# raspdancer21_1_0.net
KiCad netlist of a schematic drawn in EAGLE
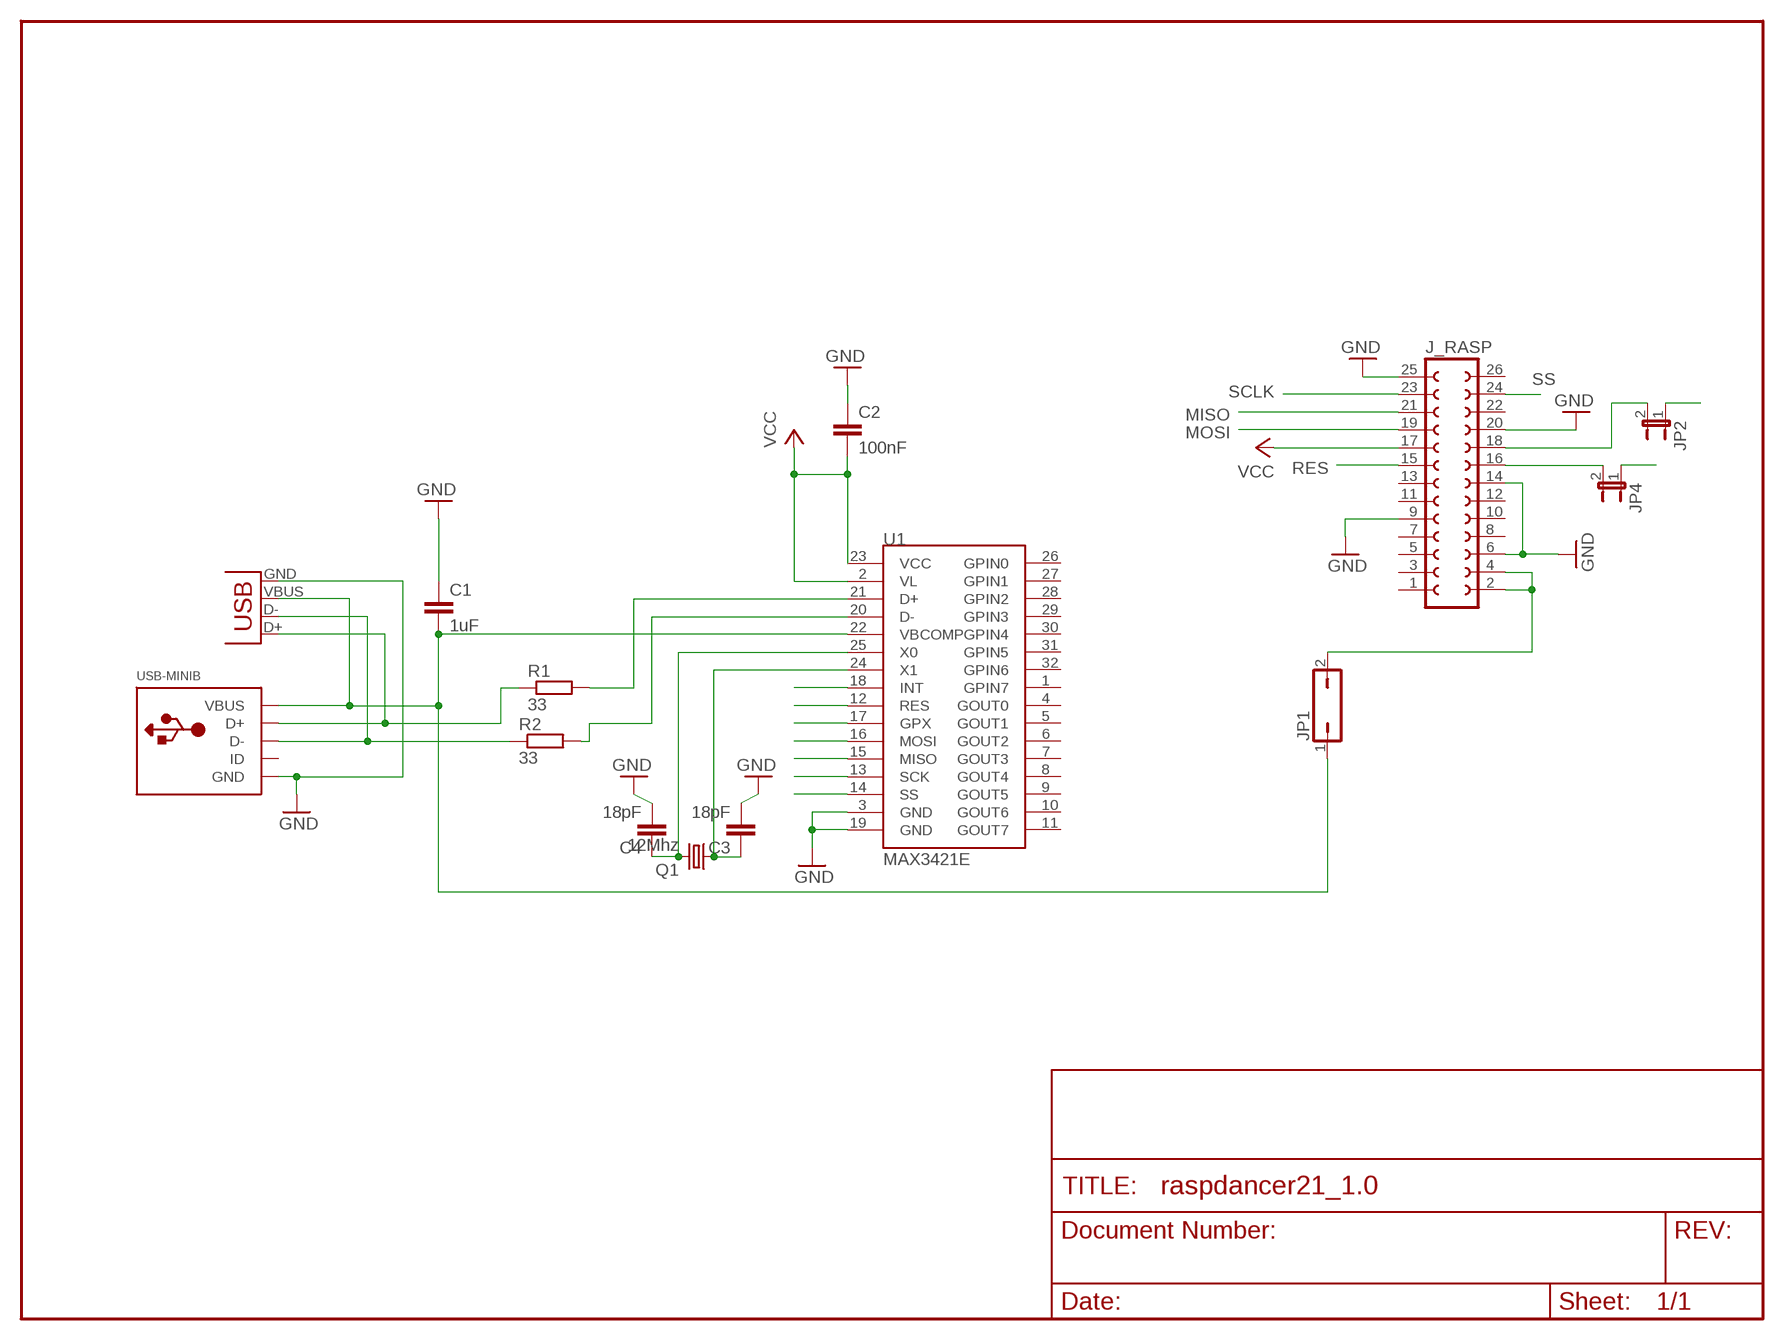
[diagram p0: schematic, sheet 1]

(export (version "E")
  (design (tool "Eeschema 10.0.6"))
  (components
    (comp (ref "C1")
      (value "1uF")
      (footprint "eagle-import:C1206")
      (libsource (lib "eagle-import") (part "C1206"))
    )
    (comp (ref "C2")
      (value "100nF")
      (footprint "eagle-import:C1206")
      (libsource (lib "eagle-import") (part "C1206"))
    )
    (comp (ref "C3")
      (value "18pF")
      (footprint "eagle-import:C1206")
      (libsource (lib "eagle-import") (part "C1206"))
    )
    (comp (ref "C4")
      (value "18pF")
      (footprint "eagle-import:C1206")
      (libsource (lib "eagle-import") (part "C1206"))
    )
    (comp (ref "JP1")
      (value "JP1Q")
      (footprint "eagle-import:JP1")
      (libsource (lib "eagle-import") (part "JP1Q"))
    )
    (comp (ref "JP2")
      (value "JUMPER-2-OLDSMD-NO")
      (footprint "eagle-import:SJ_2S-NO")
      (libsource (lib "eagle-import") (part "JUMPER-2-OLDSMD-NO"))
    )
    (comp (ref "JP4")
      (value "JUMPER-2-OLDSMD-NO")
      (footprint "eagle-import:SJ_2S-NO")
      (libsource (lib "eagle-import") (part "JUMPER-2-OLDSMD-NO"))
    )
    (comp (ref "JP5")
      (value "USB-A-S")
      (footprint "eagle-import:USB-A-S")
      (libsource (lib "eagle-import") (part "USB-A-S"))
    )
    (comp (ref "J_RASP")
      (value "FE13-2")
      (footprint "eagle-import:FE13-2")
      (libsource (lib "eagle-import") (part "FE13-2"))
    )
    (comp (ref "Q1")
      (value "12Mhz")
      (footprint "eagle-import:CTS406")
      (libsource (lib "eagle-import") (part "CRYSTALCTS406"))
    )
    (comp (ref "R1")
      (value "33")
      (footprint "eagle-import:R1206")
      (libsource (lib "eagle-import") (part "R1206"))
    )
    (comp (ref "R2")
      (value "33")
      (footprint "eagle-import:R1206")
      (libsource (lib "eagle-import") (part "R1206"))
    )
    (comp (ref "U1")
      (value "MAX3421E")
      (footprint "eagle-import:TQFP32-5MM")
      (libsource (lib "eagle-import") (part "MAX3421ESMD"))
    )
    (comp (ref "USB-MINIB")
      (value "USBMINIB")
      (footprint "eagle-import:USB-MINIB")
      (libsource (lib "eagle-import") (part "USBMINIB"))
    )
  )
  (nets
    (net (code "1") (name "/GPX") (class "Default")
      (node (ref "JP4") (pin "1") (pinfunction "1_1") (pintype "passive"))
      (node (ref "U1") (pin "17") (pinfunction "GPX_17") (pintype "bidirectional"))
    )
    (net (code "2") (name "/INT") (class "Default")
      (node (ref "JP2") (pin "1") (pinfunction "1_1") (pintype "passive"))
      (node (ref "U1") (pin "18") (pinfunction "INT_18") (pintype "bidirectional"))
    )
    (net (code "3") (name "/MISO") (class "Default")
      (node (ref "J_RASP") (pin "21") (pinfunction "21_21") (pintype "passive"))
      (node (ref "U1") (pin "15") (pinfunction "MISO_15") (pintype "bidirectional"))
    )
    (net (code "4") (name "/MOSI") (class "Default")
      (node (ref "J_RASP") (pin "19") (pinfunction "19_19") (pintype "passive"))
      (node (ref "U1") (pin "16") (pinfunction "MOSI_16") (pintype "bidirectional"))
    )
    (net (code "5") (name "/RES") (class "Default")
      (node (ref "J_RASP") (pin "15") (pinfunction "15_15") (pintype "passive"))
      (node (ref "U1") (pin "12") (pinfunction "RES_12") (pintype "bidirectional"))
    )
    (net (code "6") (name "/SCLK") (class "Default")
      (node (ref "J_RASP") (pin "23") (pinfunction "23_23") (pintype "passive"))
      (node (ref "U1") (pin "13") (pinfunction "SCK_13") (pintype "bidirectional"))
    )
    (net (code "7") (name "/SS") (class "Default")
      (node (ref "J_RASP") (pin "24") (pinfunction "24_24") (pintype "passive"))
      (node (ref "U1") (pin "14") (pinfunction "SS_14") (pintype "bidirectional"))
    )
    (net (code "8") (name "GND") (class "Default")
      (node (ref "C1") (pin "1") (pinfunction "1_1") (pintype "passive"))
      (node (ref "C2") (pin "1") (pinfunction "1_1") (pintype "passive"))
      (node (ref "C3") (pin "2") (pinfunction "2_2") (pintype "passive"))
      (node (ref "C4") (pin "2") (pinfunction "2_2") (pintype "passive"))
      (node (ref "JP5") (pin "GND") (pinfunction "GND_GND") (pintype "bidirectional"))
      (node (ref "J_RASP") (pin "14") (pinfunction "14_14") (pintype "passive"))
      (node (ref "J_RASP") (pin "20") (pinfunction "20_20") (pintype "passive"))
      (node (ref "J_RASP") (pin "25") (pinfunction "25_25") (pintype "passive"))
      (node (ref "J_RASP") (pin "6") (pinfunction "6_6") (pintype "passive"))
      (node (ref "J_RASP") (pin "9") (pinfunction "9_9") (pintype "passive"))
      (node (ref "U1") (pin "19") (pinfunction "GND_19") (pintype "bidirectional"))
      (node (ref "U1") (pin "3") (pinfunction "GND_3") (pintype "bidirectional"))
      (node (ref "USB-MINIB") (pin "GND") (pinfunction "GND_GND") (pintype "power_in"))
    )
    (net (code "9") (name "Net-(JP1-Pad2)") (class "Default")
      (node (ref "JP1") (pin "2") (pinfunction "2_2") (pintype "passive"))
      (node (ref "J_RASP") (pin "2") (pinfunction "2_2") (pintype "passive"))
      (node (ref "J_RASP") (pin "4") (pinfunction "4_4") (pintype "passive"))
    )
    (net (code "10") (name "Net-(JP2-Pad2)") (class "Default")
      (node (ref "JP2") (pin "2") (pinfunction "2_2") (pintype "passive"))
      (node (ref "J_RASP") (pin "18") (pinfunction "18_18") (pintype "passive"))
    )
    (net (code "11") (name "Net-(JP4-Pad2)") (class "Default")
      (node (ref "JP4") (pin "2") (pinfunction "2_2") (pintype "passive"))
      (node (ref "J_RASP") (pin "16") (pinfunction "16_16") (pintype "passive"))
    )
    (net (code "12") (name "Net-(JP5-PadD+)") (class "Default")
      (node (ref "JP5") (pin "D+") (pinfunction "D+_D+") (pintype "bidirectional"))
      (node (ref "R1") (pin "1") (pinfunction "1_1") (pintype "passive"))
      (node (ref "USB-MINIB") (pin "D+") (pinfunction "D+_D+") (pintype "bidirectional"))
    )
    (net (code "13") (name "Net-(JP5-PadD-)") (class "Default")
      (node (ref "JP5") (pin "D-") (pinfunction "D-_D-") (pintype "bidirectional"))
      (node (ref "R2") (pin "1") (pinfunction "1_1") (pintype "passive"))
      (node (ref "USB-MINIB") (pin "D-") (pinfunction "D-_D-") (pintype "bidirectional"))
    )
    (net (code "14") (name "Net-(Q1-2)") (class "Default")
      (node (ref "C4") (pin "1") (pinfunction "1_1") (pintype "passive"))
      (node (ref "Q1") (pin "3") (pinfunction "2_3") (pintype "passive"))
      (node (ref "U1") (pin "25") (pinfunction "X0_25") (pintype "bidirectional"))
    )
    (net (code "15") (name "Net-(U1-D+)") (class "Default")
      (node (ref "R1") (pin "2") (pinfunction "2_2") (pintype "passive"))
      (node (ref "U1") (pin "21") (pinfunction "D+_21") (pintype "bidirectional"))
    )
    (net (code "16") (name "Net-(U1-D-)") (class "Default")
      (node (ref "R2") (pin "2") (pinfunction "2_2") (pintype "passive"))
      (node (ref "U1") (pin "20") (pinfunction "D-_20") (pintype "bidirectional"))
    )
    (net (code "17") (name "Net-(U1-VBCOMP)") (class "Default")
      (node (ref "C1") (pin "2") (pinfunction "2_2") (pintype "passive"))
      (node (ref "JP1") (pin "1") (pinfunction "1_1") (pintype "passive"))
      (node (ref "JP5") (pin "VBUS") (pinfunction "VBUS_VBUS") (pintype "bidirectional"))
      (node (ref "U1") (pin "22") (pinfunction "VBCOMP_22") (pintype "bidirectional"))
      (node (ref "USB-MINIB") (pin "VBUS") (pinfunction "VBUS_VBUS") (pintype "power_in"))
    )
    (net (code "18") (name "Net-(U1-X1)") (class "Default")
      (node (ref "C3") (pin "1") (pinfunction "1_1") (pintype "passive"))
      (node (ref "Q1") (pin "1") (pinfunction "1_1") (pintype "passive"))
      (node (ref "U1") (pin "24") (pinfunction "X1_24") (pintype "bidirectional"))
    )
    (net (code "19") (name "VCC") (class "Default")
      (node (ref "C2") (pin "2") (pinfunction "2_2") (pintype "passive"))
      (node (ref "J_RASP") (pin "17") (pinfunction "17_17") (pintype "passive"))
      (node (ref "U1") (pin "2") (pinfunction "VL_2") (pintype "bidirectional"))
      (node (ref "U1") (pin "23") (pinfunction "VCC_23") (pintype "bidirectional"))
    )
    (net (code "20") (name "unconnected-(J_RASP-Pad1)") (class "Default")
      (node (ref "J_RASP") (pin "1") (pinfunction "1_1") (pintype "passive"))
    )
    (net (code "21") (name "unconnected-(J_RASP-Pad3)") (class "Default")
      (node (ref "J_RASP") (pin "3") (pinfunction "3_3") (pintype "passive"))
    )
    (net (code "22") (name "unconnected-(J_RASP-Pad5)") (class "Default")
      (node (ref "J_RASP") (pin "5") (pinfunction "5_5") (pintype "passive"))
    )
    (net (code "23") (name "unconnected-(J_RASP-Pad7)") (class "Default")
      (node (ref "J_RASP") (pin "7") (pinfunction "7_7") (pintype "passive"))
    )
    (net (code "24") (name "unconnected-(J_RASP-Pad8)") (class "Default")
      (node (ref "J_RASP") (pin "8") (pinfunction "8_8") (pintype "passive"))
    )
    (net (code "25") (name "unconnected-(J_RASP-Pad10)") (class "Default")
      (node (ref "J_RASP") (pin "10") (pinfunction "10_10") (pintype "passive"))
    )
    (net (code "26") (name "unconnected-(J_RASP-Pad11)") (class "Default")
      (node (ref "J_RASP") (pin "11") (pinfunction "11_11") (pintype "passive"))
    )
    (net (code "27") (name "unconnected-(J_RASP-Pad12)") (class "Default")
      (node (ref "J_RASP") (pin "12") (pinfunction "12_12") (pintype "passive"))
    )
    (net (code "28") (name "unconnected-(J_RASP-Pad13)") (class "Default")
      (node (ref "J_RASP") (pin "13") (pinfunction "13_13") (pintype "passive"))
    )
    (net (code "29") (name "unconnected-(J_RASP-Pad22)") (class "Default")
      (node (ref "J_RASP") (pin "22") (pinfunction "22_22") (pintype "passive"))
    )
    (net (code "30") (name "unconnected-(J_RASP-Pad26)") (class "Default")
      (node (ref "J_RASP") (pin "26") (pinfunction "26_26") (pintype "passive"))
    )
    (net (code "31") (name "unconnected-(U1-GOUT0-Pad4)") (class "Default")
      (node (ref "U1") (pin "4") (pinfunction "GOUT0_4") (pintype "bidirectional"))
    )
    (net (code "32") (name "unconnected-(U1-GOUT1-Pad5)") (class "Default")
      (node (ref "U1") (pin "5") (pinfunction "GOUT1_5") (pintype "bidirectional"))
    )
    (net (code "33") (name "unconnected-(U1-GOUT2-Pad6)") (class "Default")
      (node (ref "U1") (pin "6") (pinfunction "GOUT2_6") (pintype "bidirectional"))
    )
    (net (code "34") (name "unconnected-(U1-GOUT3-Pad7)") (class "Default")
      (node (ref "U1") (pin "7") (pinfunction "GOUT3_7") (pintype "bidirectional"))
    )
    (net (code "35") (name "unconnected-(U1-GOUT4-Pad8)") (class "Default")
      (node (ref "U1") (pin "8") (pinfunction "GOUT4_8") (pintype "bidirectional"))
    )
    (net (code "36") (name "unconnected-(U1-GOUT5-Pad9)") (class "Default")
      (node (ref "U1") (pin "9") (pinfunction "GOUT5_9") (pintype "bidirectional"))
    )
    (net (code "37") (name "unconnected-(U1-GOUT6-Pad10)") (class "Default")
      (node (ref "U1") (pin "10") (pinfunction "GOUT6_10") (pintype "bidirectional"))
    )
    (net (code "38") (name "unconnected-(U1-GOUT7-Pad11)") (class "Default")
      (node (ref "U1") (pin "11") (pinfunction "GOUT7_11") (pintype "bidirectional"))
    )
    (net (code "39") (name "unconnected-(U1-GPIN0-Pad26)") (class "Default")
      (node (ref "U1") (pin "26") (pinfunction "GPIN0_26") (pintype "bidirectional"))
    )
    (net (code "40") (name "unconnected-(U1-GPIN1-Pad27)") (class "Default")
      (node (ref "U1") (pin "27") (pinfunction "GPIN1_27") (pintype "bidirectional"))
    )
    (net (code "41") (name "unconnected-(U1-GPIN2-Pad28)") (class "Default")
      (node (ref "U1") (pin "28") (pinfunction "GPIN2_28") (pintype "bidirectional"))
    )
    (net (code "42") (name "unconnected-(U1-GPIN3-Pad29)") (class "Default")
      (node (ref "U1") (pin "29") (pinfunction "GPIN3_29") (pintype "bidirectional"))
    )
    (net (code "43") (name "unconnected-(U1-GPIN4-Pad30)") (class "Default")
      (node (ref "U1") (pin "30") (pinfunction "GPIN4_30") (pintype "bidirectional"))
    )
    (net (code "44") (name "unconnected-(U1-GPIN5-Pad31)") (class "Default")
      (node (ref "U1") (pin "31") (pinfunction "GPIN5_31") (pintype "bidirectional"))
    )
    (net (code "45") (name "unconnected-(U1-GPIN6-Pad32)") (class "Default")
      (node (ref "U1") (pin "32") (pinfunction "GPIN6_32") (pintype "bidirectional"))
    )
    (net (code "46") (name "unconnected-(U1-GPIN7-Pad1)") (class "Default")
      (node (ref "U1") (pin "1") (pinfunction "GPIN7_1") (pintype "bidirectional"))
    )
    (net (code "47") (name "unconnected-(USB-MINIB-PadID)") (class "Default")
      (node (ref "USB-MINIB") (pin "ID") (pinfunction "ID_ID") (pintype "bidirectional"))
    )
  )
)
